# 00A-003.net
KiCad netlist of a schematic drawn in EAGLE
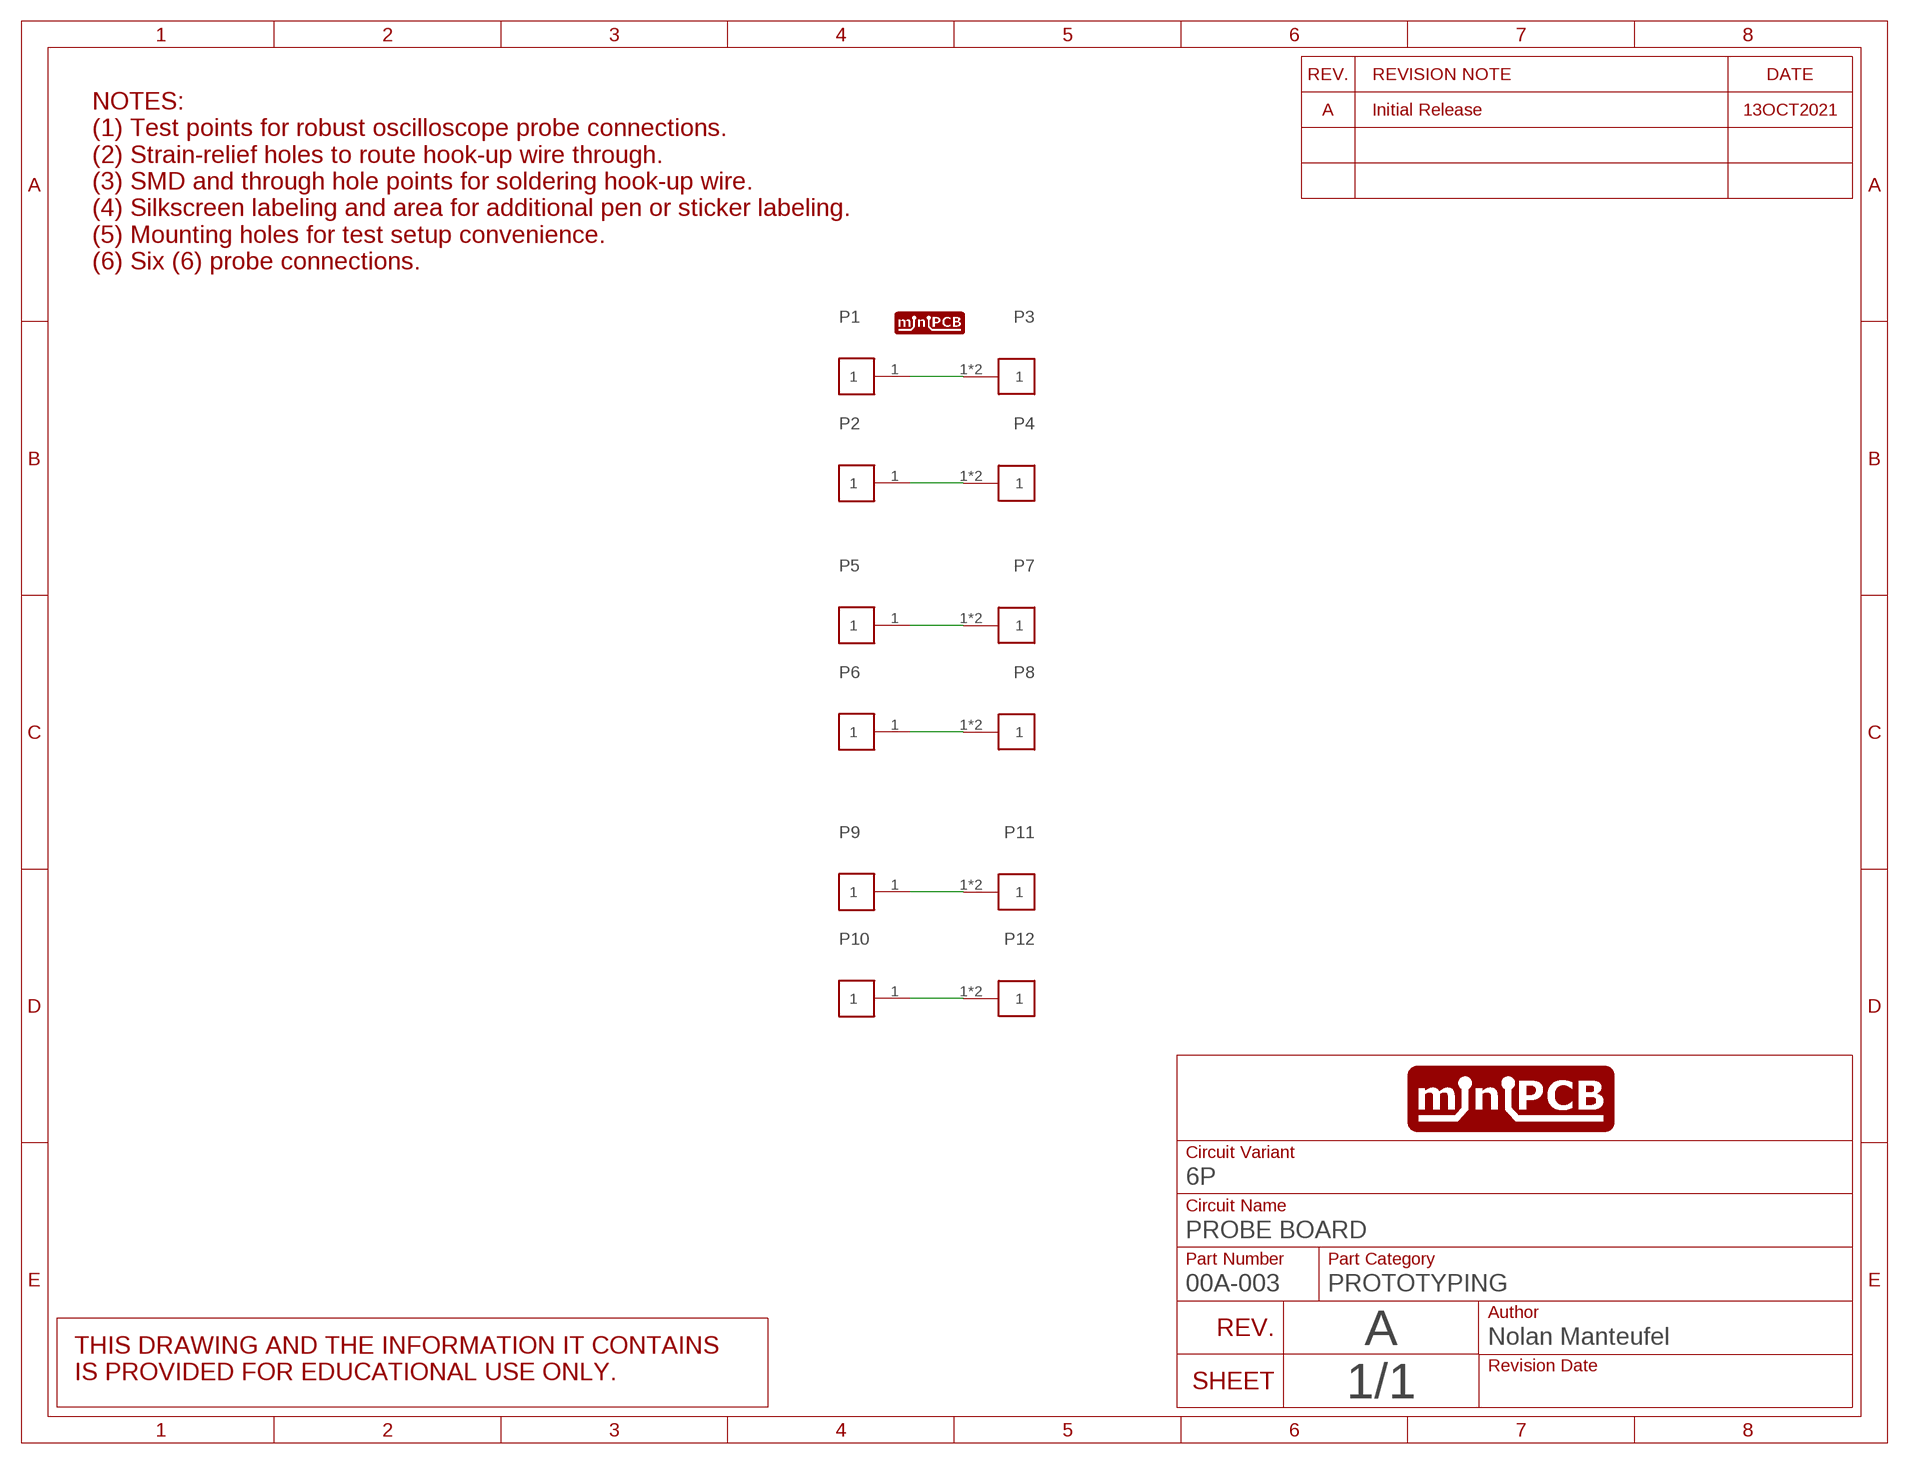
[diagram p0: schematic, sheet 1]

(export (version "E")
  (design (tool "Eeschema 10.0.6"))
  (components
    (comp (ref "P1")
      (value "PINS_1KE_5000")
      (footprint "eagle-import:PINS_1_TESTPOINT_KE5000")
      (libsource (lib "eagle-import") (part "PINS_1KE_5000"))
    )
    (comp (ref "P2")
      (value "PINS_1KE_5000")
      (footprint "eagle-import:PINS_1_TESTPOINT_KE5000")
      (libsource (lib "eagle-import") (part "PINS_1KE_5000"))
    )
    (comp (ref "P3")
      (value "PINS_124AWG")
      (footprint "eagle-import:PINS_1_1MM")
      (libsource (lib "eagle-import") (part "PINS_124AWG"))
    )
    (comp (ref "P4")
      (value "PINS_124AWG")
      (footprint "eagle-import:PINS_1_1MM")
      (libsource (lib "eagle-import") (part "PINS_124AWG"))
    )
    (comp (ref "P5")
      (value "PINS_1KE_5000")
      (footprint "eagle-import:PINS_1_TESTPOINT_KE5000")
      (libsource (lib "eagle-import") (part "PINS_1KE_5000"))
    )
    (comp (ref "P6")
      (value "PINS_1KE_5000")
      (footprint "eagle-import:PINS_1_TESTPOINT_KE5000")
      (libsource (lib "eagle-import") (part "PINS_1KE_5000"))
    )
    (comp (ref "P7")
      (value "PINS_124AWG")
      (footprint "eagle-import:PINS_1_1MM")
      (libsource (lib "eagle-import") (part "PINS_124AWG"))
    )
    (comp (ref "P8")
      (value "PINS_124AWG")
      (footprint "eagle-import:PINS_1_1MM")
      (libsource (lib "eagle-import") (part "PINS_124AWG"))
    )
    (comp (ref "P9")
      (value "PINS_1KE_5000")
      (footprint "eagle-import:PINS_1_TESTPOINT_KE5000")
      (libsource (lib "eagle-import") (part "PINS_1KE_5000"))
    )
    (comp (ref "P10")
      (value "PINS_1KE_5000")
      (footprint "eagle-import:PINS_1_TESTPOINT_KE5000")
      (libsource (lib "eagle-import") (part "PINS_1KE_5000"))
    )
    (comp (ref "P11")
      (value "PINS_124AWG")
      (footprint "eagle-import:PINS_1_1MM")
      (libsource (lib "eagle-import") (part "PINS_124AWG"))
    )
    (comp (ref "P12")
      (value "PINS_124AWG")
      (footprint "eagle-import:PINS_1_1MM")
      (libsource (lib "eagle-import") (part "PINS_124AWG"))
    )
    (comp (ref "U$1")
      (value "MINIPCB_LOGO")
      (footprint "eagle-import:MINIPCB-LOGO")
      (libsource (lib "eagle-import") (part "MINIPCB_LOGO"))
    )
  )
  (nets
    (net (code "1") (name "Net-(P1-Pad1)") (class "Default")
      (node (ref "P1") (pin "1") (pinfunction "1_1") (pintype "bidirectional"))
      (node (ref "P3") (pin "1") (pinfunction "1_1") (pintype "bidirectional"))
      (node (ref "P3") (pin "2") (pinfunction "1_2") (pintype "bidirectional"))
    )
    (net (code "2") (name "Net-(P2-Pad1)") (class "Default")
      (node (ref "P2") (pin "1") (pinfunction "1_1") (pintype "bidirectional"))
      (node (ref "P4") (pin "1") (pinfunction "1_1") (pintype "bidirectional"))
      (node (ref "P4") (pin "2") (pinfunction "1_2") (pintype "bidirectional"))
    )
    (net (code "3") (name "Net-(P5-Pad1)") (class "Default")
      (node (ref "P5") (pin "1") (pinfunction "1_1") (pintype "bidirectional"))
      (node (ref "P7") (pin "1") (pinfunction "1_1") (pintype "bidirectional"))
      (node (ref "P7") (pin "2") (pinfunction "1_2") (pintype "bidirectional"))
    )
    (net (code "4") (name "Net-(P6-Pad1)") (class "Default")
      (node (ref "P6") (pin "1") (pinfunction "1_1") (pintype "bidirectional"))
      (node (ref "P8") (pin "1") (pinfunction "1_1") (pintype "bidirectional"))
      (node (ref "P8") (pin "2") (pinfunction "1_2") (pintype "bidirectional"))
    )
    (net (code "5") (name "Net-(P10-Pad1)") (class "Default")
      (node (ref "P10") (pin "1") (pinfunction "1_1") (pintype "bidirectional"))
      (node (ref "P12") (pin "1") (pinfunction "1_1") (pintype "bidirectional"))
      (node (ref "P12") (pin "2") (pinfunction "1_2") (pintype "bidirectional"))
    )
    (net (code "6") (name "Net-(P11-1-Pad2)") (class "Default")
      (node (ref "P11") (pin "1") (pinfunction "1_1") (pintype "bidirectional"))
      (node (ref "P11") (pin "2") (pinfunction "1_2") (pintype "bidirectional"))
      (node (ref "P9") (pin "1") (pinfunction "1_1") (pintype "bidirectional"))
    )
  )
)
